# rotary_sewing.net
KiCad netlist of a schematic drawn in EAGLE
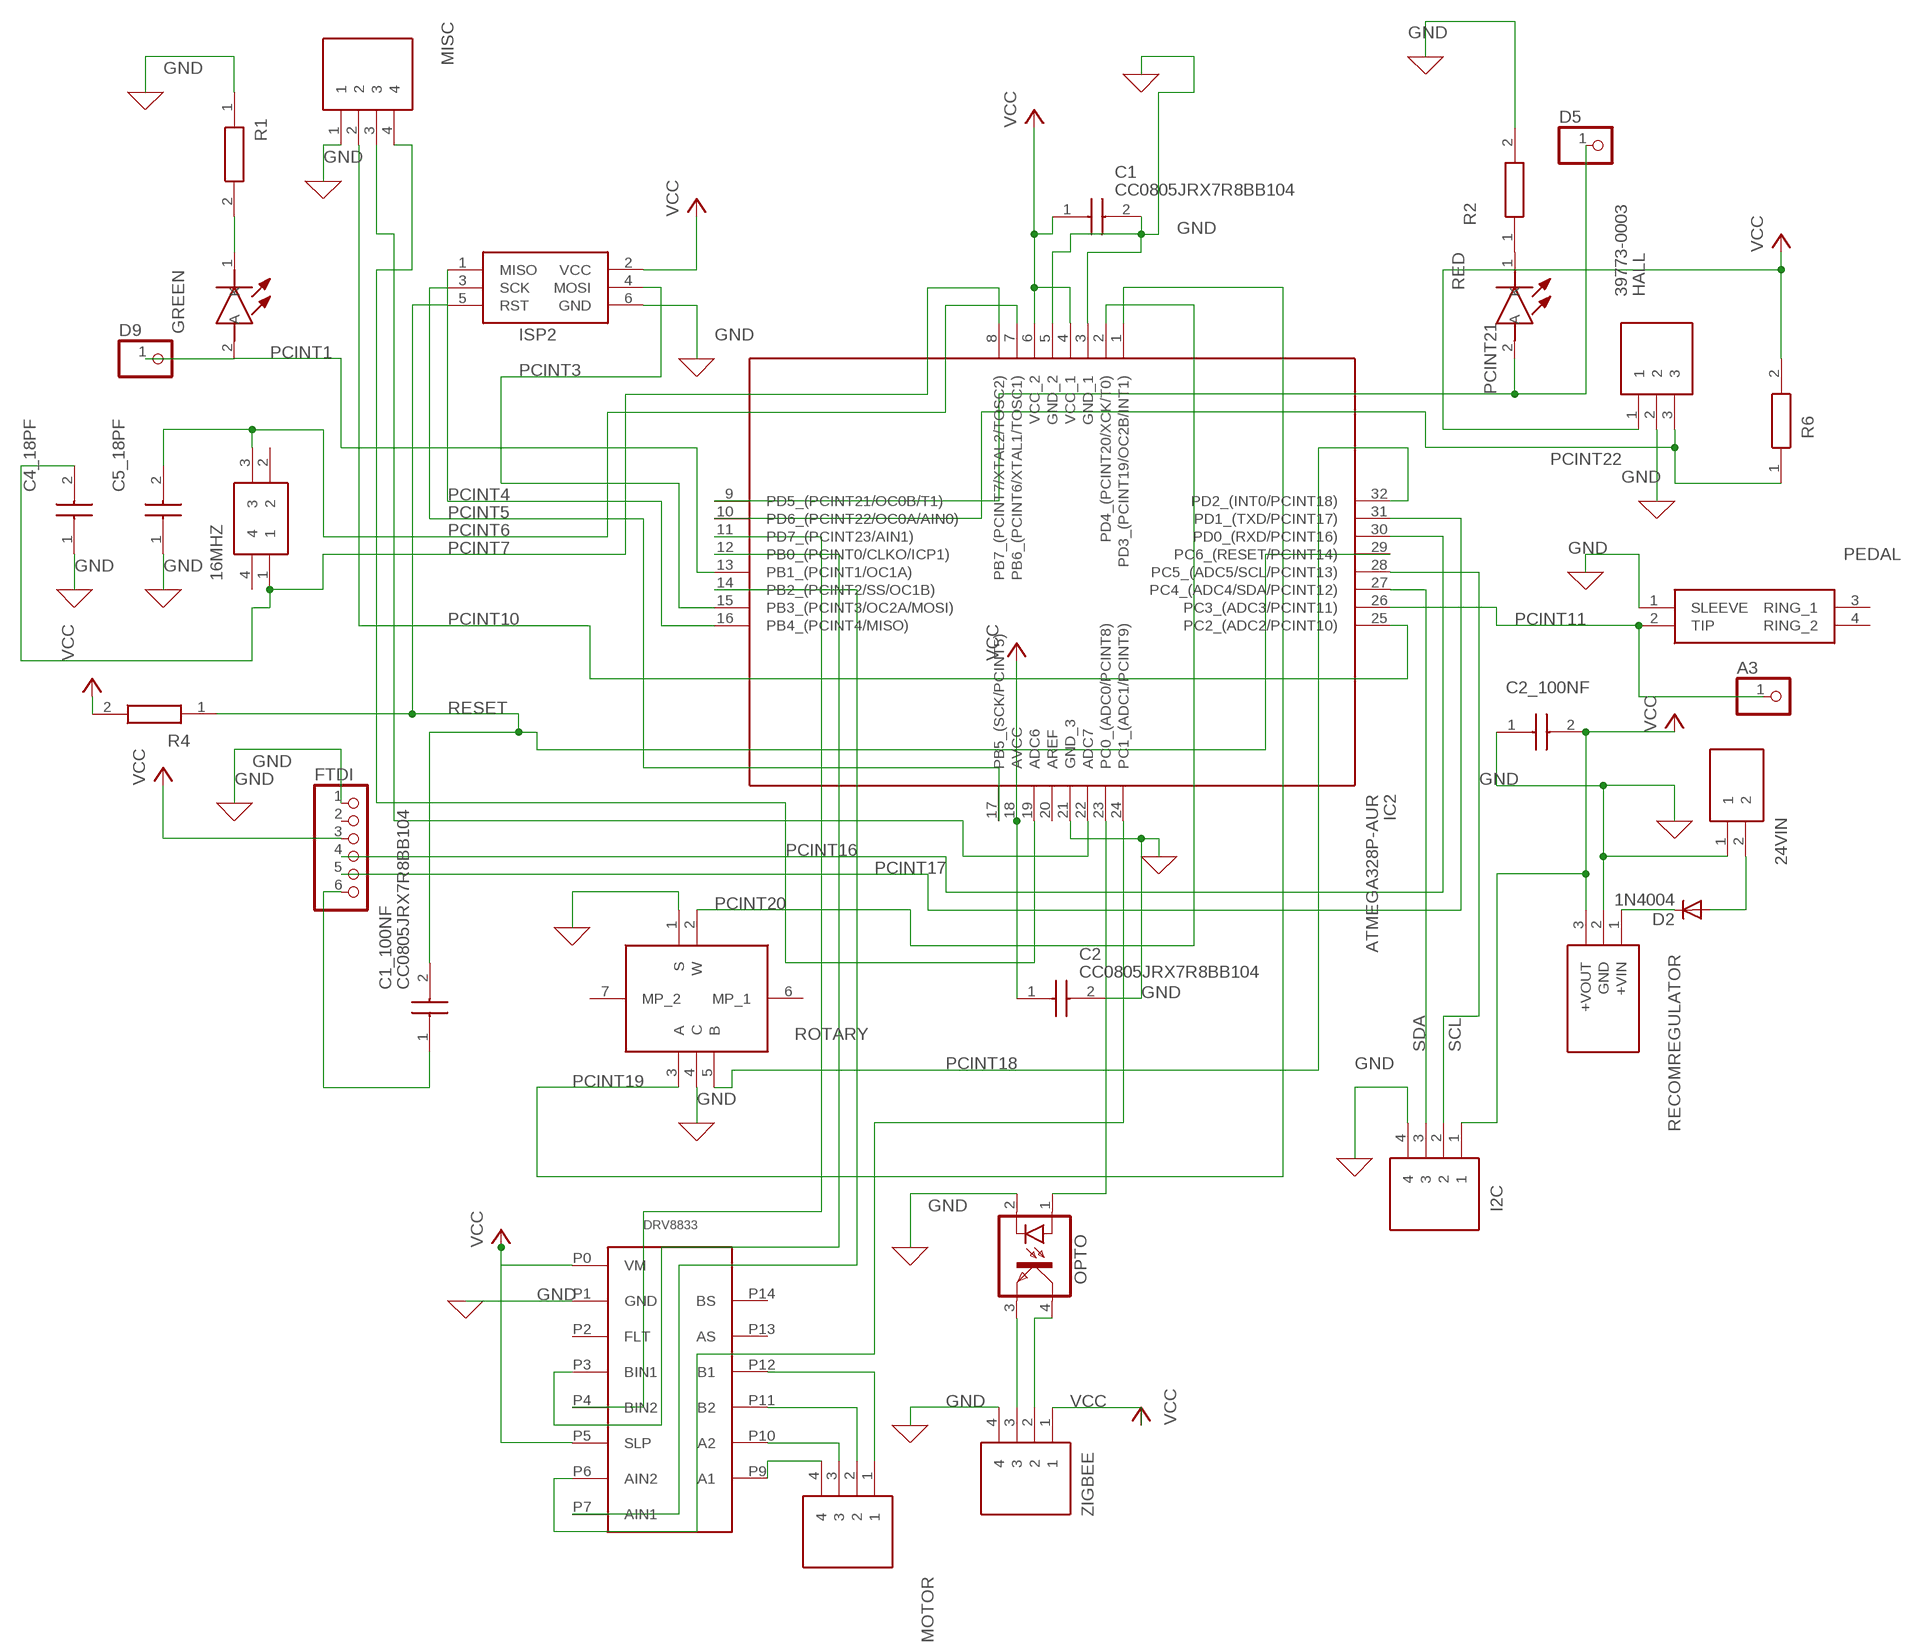
[diagram p0: schematic, sheet 1]

(export (version "E")
  (design (tool "Eeschema 10.0.6"))
  (components
    (comp (ref "16MHZ")
      (value "403C11E16M00000")
      (footprint "eagle-import:403C1XA32M00000")
      (fields (field (name "MOUSER_PART_NUMBER") "774-403C11E16M0"))
      (libsource (lib "eagle-import") (part "403C11E16M00000"))
    )
    (comp (ref "24VIN")
      (value "39773-0002")
      (footprint "eagle-import:SHDR2W110P0X254_1X2_554X650X10")
      (fields (field (name "MOUSER_PART_NUMBER") "538-39773-0002"))
      (libsource (lib "eagle-import") (part "39773-0002"))
    )
    (comp (ref "A3")
      (value "PINHD-1X1")
      (footprint "eagle-import:1X01")
      (libsource (lib "eagle-import") (part "PINHD-1X1"))
    )
    (comp (ref "C1")
      (value "CC0805JRX7R8BB104")
      (footprint "eagle-import:CAPC2012X135N")
      (fields (field (name "MOUSER_PART_NUMBER") "603-CC805JRX7R8BB104"))
      (libsource (lib "eagle-import") (part "CC0805JRX7R8BB104"))
    )
    (comp (ref "C1_100NF")
      (value "CC0805JRX7R8BB104")
      (footprint "eagle-import:CAPC2012X135N")
      (fields (field (name "MOUSER_PART_NUMBER") "603-CC805JRX7R8BB104"))
      (libsource (lib "eagle-import") (part "CC0805JRX7R8BB104"))
    )
    (comp (ref "C2")
      (value "CC0805JRX7R8BB104")
      (footprint "eagle-import:CAPC2012X135N")
      (fields (field (name "MOUSER_PART_NUMBER") "603-CC805JRX7R8BB104"))
      (libsource (lib "eagle-import") (part "CC0805JRX7R8BB104"))
    )
    (comp (ref "C2_100NF")
      (value "CC0805JRX7R8BB104")
      (footprint "eagle-import:CAPC2012X135N")
      (fields (field (name "MOUSER_PART_NUMBER") "603-CC805JRX7R8BB104"))
      (libsource (lib "eagle-import") (part "CC0805JRX7R8BB104"))
    )
    (comp (ref "C4_18PF")
      (value "C0805C180J5GACTU")
      (footprint "eagle-import:CAPC2012X88N")
      (fields (field (name "MOUSER_PART_NUMBER") "80-C0805C180J5G"))
      (libsource (lib "eagle-import") (part "C0805C180J5GACTU"))
    )
    (comp (ref "C5_18PF")
      (value "C0805C180J5GACTU")
      (footprint "eagle-import:CAPC2012X88N")
      (fields (field (name "MOUSER_PART_NUMBER") "80-C0805C180J5G"))
      (libsource (lib "eagle-import") (part "C0805C180J5GACTU"))
    )
    (comp (ref "D2")
      (value "1N4004")
      (footprint "eagle-import:DO41-10")
      (libsource (lib "eagle-import") (part "1N4004"))
    )
    (comp (ref "D5")
      (value "PINHD-1X1")
      (footprint "eagle-import:1X01")
      (libsource (lib "eagle-import") (part "PINHD-1X1"))
    )
    (comp (ref "D9")
      (value "PINHD-1X1")
      (footprint "eagle-import:1X01")
      (libsource (lib "eagle-import") (part "PINHD-1X1"))
    )
    (comp (ref "DRV8833")
      (value "DRV8833")
      (footprint "eagle-import:DRV8833")
      (libsource (lib "eagle-import") (part "DRV8833"))
    )
    (comp (ref "FTDI")
      (value "PINHD-1X6")
      (footprint "eagle-import:1X06")
      (libsource (lib "eagle-import") (part "PINHD-1X6"))
    )
    (comp (ref "GREEN")
      (value "LTST-C171GKT")
      (footprint "eagle-import:LEDC2012X90N")
      (fields (field (name "MOUSER_PART_NUMBER") "859-LTST-C171GKT"))
      (libsource (lib "eagle-import") (part "LTST-C171GKT"))
    )
    (comp (ref "HALL")
      (value "39773-0003")
      (footprint "eagle-import:SHDR3W80P0X254_1X3_808X650X101")
      (fields (field (name "MOUSER_PART_NUMBER") "538-39773-0003"))
      (libsource (lib "eagle-import") (part "39773-0003"))
    )
    (comp (ref "I2C")
      (value "39773-0004")
      (footprint "eagle-import:SHDR4W80P0X254_1X4_1062X650X10")
      (fields (field (name "MOUSER_PART_NUMBER") "538-39773-0004"))
      (libsource (lib "eagle-import") (part "39773-0004"))
    )
    (comp (ref "IC2")
      (value "ATMEGA328P-AUR")
      (footprint "eagle-import:QFP80P900X900X120-32N")
      (fields (field (name "MOUSER_PART_NUMBER") "556-ATMEGA328P-AUR"))
      (libsource (lib "eagle-import") (part "ATMEGA328P-AUR"))
    )
    (comp (ref "ISP2")
      (value "AVRISP-6")
      (footprint "eagle-import:AVRISP")
      (libsource (lib "eagle-import") (part "AVRISP-6"))
    )
    (comp (ref "MISC")
      (value "39773-0004")
      (footprint "eagle-import:SHDR4W80P0X254_1X4_1062X650X10")
      (fields (field (name "MOUSER_PART_NUMBER") "538-39773-0004"))
      (libsource (lib "eagle-import") (part "39773-0004"))
    )
    (comp (ref "MOTOR")
      (value "39773-0004")
      (footprint "eagle-import:SHDR4W80P0X254_1X4_1062X650X10")
      (fields (field (name "MOUSER_PART_NUMBER") "538-39773-0004"))
      (libsource (lib "eagle-import") (part "39773-0004"))
    )
    (comp (ref "OPTO")
      (value "PC817")
      (footprint "eagle-import:DIL04")
      (fields (field (name "MPN") "PC817X4J000F"))
      (libsource (lib "eagle-import") (part "PC817"))
    )
    (comp (ref "PEDAL")
      (value "SJ2-3574A-SMT-TR")
      (footprint "eagle-import:SJ23574ASMTTR")
      (fields (field (name "MOUSER_PART_NUMBER") "490-SJ2-3574A-SMT-TR"))
      (libsource (lib "eagle-import") (part "SJ2-3574A-SMT-TR"))
    )
    (comp (ref "R1")
      (value "RMC1_10K1001FTP")
      (footprint "eagle-import:RESC2012X65N")
      (fields
        (field (name "MANUFACTURER_PART_NUMBER") "RMC1/10K1001FTP")
        (field (name "MOUSER_PART_NUMBER") "791-RMC1/10K1001FTP")
      )
      (libsource (lib "eagle-import") (part "RMC1_10K1001FTP"))
    )
    (comp (ref "R2")
      (value "RMC1_10K1001FTP")
      (footprint "eagle-import:RESC2012X65N")
      (fields
        (field (name "MANUFACTURER_PART_NUMBER") "RMC1/10K1001FTP")
        (field (name "MOUSER_PART_NUMBER") "791-RMC1/10K1001FTP")
      )
      (libsource (lib "eagle-import") (part "RMC1_10K1001FTP"))
    )
    (comp (ref "R4")
      (value "ERA-6AED103V")
      (footprint "eagle-import:RESC2012X60N")
      (fields (field (name "MOUSER_PART_NUMBER") "667-ERA-6AED103V"))
      (libsource (lib "eagle-import") (part "ERA-6AED103V"))
    )
    (comp (ref "R6")
      (value "ERA-6AED103V")
      (footprint "eagle-import:RESC2012X60N")
      (fields (field (name "MOUSER_PART_NUMBER") "667-ERA-6AED103V"))
      (libsource (lib "eagle-import") (part "ERA-6AED103V"))
    )
    (comp (ref "RECOMREGULATOR")
      (value "R-78E3.3-1.0")
      (footprint "eagle-import:R-78E3.3-1.0")
      (fields (field (name "MOUSER_PART_NUMBER") "919-R-78E3.3-1.0"))
      (libsource (lib "eagle-import") (part "R-78E3.3-1.0"))
    )
    (comp (ref "RED")
      (value "LTST-C171KRKT")
      (footprint "eagle-import:LEDM2012X90N")
      (fields (field (name "MOUSER_PART_NUMBER") "859-LTST-C171KRKT"))
      (libsource (lib "eagle-import") (part "LTST-C171KRKT"))
    )
    (comp (ref "ROTARY")
      (value "PEC11L-4220F-S0015")
      (footprint "eagle-import:PEC11L4220FS0015")
      (fields (field (name "MOUSER_PART_NUMBER") "652-PEC11L4220FS0015"))
      (libsource (lib "eagle-import") (part "PEC11L-4220F-S0015"))
    )
    (comp (ref "ZIGBEE")
      (value "39773-0004")
      (footprint "eagle-import:SHDR4W80P0X254_1X4_1062X650X10")
      (fields (field (name "MOUSER_PART_NUMBER") "538-39773-0004"))
      (libsource (lib "eagle-import") (part "39773-0004"))
    )
  )
  (nets
    (net (code "1") (name "/PCINT1") (class "Default")
      (node (ref "D9") (pin "1") (pinfunction "1_1") (pintype "passive"))
      (node (ref "GREEN") (pin "2") (pinfunction "A_2") (pintype "bidirectional"))
      (node (ref "IC2") (pin "13") (pinfunction "PB1_(PCINT1/OC1A)_13") (pintype "input"))
    )
    (net (code "2") (name "/PCINT3") (class "Default")
      (node (ref "IC2") (pin "15") (pinfunction "PB3_(PCINT3/OC2A/MOSI)_15") (pintype "input"))
      (node (ref "ISP2") (pin "4") (pinfunction "MOSI_4") (pintype "output"))
    )
    (net (code "3") (name "/PCINT4") (class "Default")
      (node (ref "IC2") (pin "16") (pinfunction "PB4_(PCINT4/MISO)_16") (pintype "input"))
      (node (ref "ISP2") (pin "1") (pinfunction "MISO_1") (pintype "input"))
    )
    (net (code "4") (name "/PCINT5") (class "Default")
      (node (ref "IC2") (pin "17") (pinfunction "PB5_(SCK/PCINT5)_17") (pintype "input"))
      (node (ref "ISP2") (pin "3") (pinfunction "SCK_3") (pintype "output"))
    )
    (net (code "5") (name "/PCINT6") (class "Default")
      (node (ref "16MHZ") (pin "3") (pinfunction "3_3") (pintype "bidirectional"))
      (node (ref "C5_18PF") (pin "2") (pinfunction "2_2") (pintype "bidirectional"))
      (node (ref "IC2") (pin "7") (pinfunction "PB6_(PCINT6/XTAL1/TOSC1)_7") (pintype "input"))
    )
    (net (code "6") (name "/PCINT7") (class "Default")
      (node (ref "16MHZ") (pin "1") (pinfunction "1_1") (pintype "bidirectional"))
      (node (ref "C4_18PF") (pin "2") (pinfunction "2_2") (pintype "bidirectional"))
      (node (ref "IC2") (pin "8") (pinfunction "PB7_(PCINT7/XTAL2/TOSC2)_8") (pintype "input"))
    )
    (net (code "7") (name "/PCINT10") (class "Default")
      (node (ref "IC2") (pin "25") (pinfunction "PC2_(ADC2/PCINT10)_25") (pintype "input"))
      (node (ref "MISC") (pin "2") (pinfunction "2_2") (pintype "bidirectional"))
    )
    (net (code "8") (name "/PCINT11") (class "Default")
      (node (ref "A3") (pin "1") (pinfunction "1_1") (pintype "passive"))
      (node (ref "IC2") (pin "26") (pinfunction "PC3_(ADC3/PCINT11)_26") (pintype "input"))
      (node (ref "PEDAL") (pin "2") (pinfunction "TIP_2") (pintype "bidirectional"))
    )
    (net (code "9") (name "/PCINT16") (class "Default")
      (node (ref "FTDI") (pin "4") (pinfunction "4_4") (pintype "passive"))
      (node (ref "IC2") (pin "30") (pinfunction "PD0_(RXD/PCINT16)_30") (pintype "input"))
    )
    (net (code "10") (name "/PCINT17") (class "Default")
      (node (ref "FTDI") (pin "5") (pinfunction "5_5") (pintype "passive"))
      (node (ref "IC2") (pin "31") (pinfunction "PD1_(TXD/PCINT17)_31") (pintype "input"))
    )
    (net (code "11") (name "/PCINT18") (class "Default")
      (node (ref "IC2") (pin "32") (pinfunction "PD2_(INT0/PCINT18)_32") (pintype "input"))
      (node (ref "ROTARY") (pin "5") (pinfunction "B_5") (pintype "bidirectional"))
    )
    (net (code "12") (name "/PCINT19") (class "Default")
      (node (ref "IC2") (pin "1") (pinfunction "PD3_(PCINT19/OC2B/INT1)_1") (pintype "input"))
      (node (ref "ROTARY") (pin "3") (pinfunction "A_3") (pintype "bidirectional"))
    )
    (net (code "13") (name "/PCINT20") (class "Default")
      (node (ref "IC2") (pin "2") (pinfunction "PD4_(PCINT20/XCK/T0)_2") (pintype "input"))
      (node (ref "ROTARY") (pin "2") (pinfunction "W_2") (pintype "bidirectional"))
    )
    (net (code "14") (name "/PCINT21") (class "Default")
      (node (ref "D5") (pin "1") (pinfunction "1_1") (pintype "passive"))
      (node (ref "IC2") (pin "9") (pinfunction "PD5_(PCINT21/OC0B/T1)_9") (pintype "input"))
      (node (ref "RED") (pin "2") (pinfunction "A_2") (pintype "bidirectional"))
    )
    (net (code "15") (name "/PCINT22") (class "Default")
      (node (ref "HALL") (pin "3") (pinfunction "3_3") (pintype "bidirectional"))
      (node (ref "IC2") (pin "10") (pinfunction "PD6_(PCINT22/OC0A/AIN0)_10") (pintype "input"))
      (node (ref "R6") (pin "1") (pinfunction "1_1") (pintype "bidirectional"))
    )
    (net (code "16") (name "/RESET") (class "Default")
      (node (ref "C1_100NF") (pin "2") (pinfunction "2_2") (pintype "bidirectional"))
      (node (ref "IC2") (pin "29") (pinfunction "PC6_(RESET/PCINT14)_29") (pintype "input"))
      (node (ref "ISP2") (pin "5") (pinfunction "RST_5") (pintype "output"))
      (node (ref "R4") (pin "1") (pinfunction "1_1") (pintype "bidirectional"))
    )
    (net (code "17") (name "/SCL") (class "Default")
      (node (ref "I2C") (pin "2") (pinfunction "2_2") (pintype "bidirectional"))
      (node (ref "IC2") (pin "28") (pinfunction "PC5_(ADC5/SCL/PCINT13)_28") (pintype "input"))
    )
    (net (code "18") (name "/SDA") (class "Default")
      (node (ref "I2C") (pin "3") (pinfunction "3_3") (pintype "bidirectional"))
      (node (ref "IC2") (pin "27") (pinfunction "PC4_(ADC4/SDA/PCINT12)_27") (pintype "input"))
    )
    (net (code "19") (name "GND") (class "Default")
      (node (ref "24VIN") (pin "1") (pinfunction "1_1") (pintype "bidirectional"))
      (node (ref "C1") (pin "2") (pinfunction "2_2") (pintype "bidirectional"))
      (node (ref "C2") (pin "2") (pinfunction "2_2") (pintype "bidirectional"))
      (node (ref "C2_100NF") (pin "1") (pinfunction "1_1") (pintype "bidirectional"))
      (node (ref "C4_18PF") (pin "1") (pinfunction "1_1") (pintype "bidirectional"))
      (node (ref "C5_18PF") (pin "1") (pinfunction "1_1") (pintype "bidirectional"))
      (node (ref "DRV8833") (pin "P1") (pinfunction "GND_P1") (pintype "bidirectional"))
      (node (ref "FTDI") (pin "1") (pinfunction "1_1") (pintype "passive"))
      (node (ref "HALL") (pin "2") (pinfunction "2_2") (pintype "bidirectional"))
      (node (ref "I2C") (pin "4") (pinfunction "4_4") (pintype "bidirectional"))
      (node (ref "IC2") (pin "21") (pinfunction "GND_3_21") (pintype "power_in"))
      (node (ref "IC2") (pin "3") (pinfunction "GND_1_3") (pintype "power_in"))
      (node (ref "IC2") (pin "5") (pinfunction "GND_2_5") (pintype "power_in"))
      (node (ref "ISP2") (pin "6") (pinfunction "GND_6") (pintype "power_in"))
      (node (ref "MISC") (pin "1") (pinfunction "1_1") (pintype "bidirectional"))
      (node (ref "OPTO") (pin "2") (pinfunction "C_2") (pintype "passive"))
      (node (ref "PEDAL") (pin "1") (pinfunction "SLEEVE_1") (pintype "bidirectional"))
      (node (ref "R1") (pin "1") (pinfunction "1_1") (pintype "bidirectional"))
      (node (ref "R2") (pin "2") (pinfunction "2_2") (pintype "bidirectional"))
      (node (ref "RECOMREGULATOR") (pin "2") (pinfunction "GND_2") (pintype "bidirectional"))
      (node (ref "ROTARY") (pin "1") (pinfunction "S_1") (pintype "bidirectional"))
      (node (ref "ROTARY") (pin "4") (pinfunction "C_4") (pintype "bidirectional"))
      (node (ref "ZIGBEE") (pin "4") (pinfunction "4_4") (pintype "bidirectional"))
    )
    (net (code "20") (name "Net-(24VIN-Pad2)") (class "Default")
      (node (ref "24VIN") (pin "2") (pinfunction "2_2") (pintype "bidirectional"))
      (node (ref "D2") (pin "A") (pinfunction "A_A") (pintype "passive"))
    )
    (net (code "21") (name "Net-(C1_100NF-Pad1)") (class "Default")
      (node (ref "C1_100NF") (pin "1") (pinfunction "1_1") (pintype "bidirectional"))
      (node (ref "FTDI") (pin "6") (pinfunction "6_6") (pintype "passive"))
    )
    (net (code "22") (name "Net-(DRV8833-A1)") (class "Default")
      (node (ref "DRV8833") (pin "P9") (pinfunction "A1_P9") (pintype "bidirectional"))
      (node (ref "MOTOR") (pin "4") (pinfunction "4_4") (pintype "bidirectional"))
    )
    (net (code "23") (name "Net-(DRV8833-A2)") (class "Default")
      (node (ref "DRV8833") (pin "P10") (pinfunction "A2_P10") (pintype "bidirectional"))
      (node (ref "MOTOR") (pin "3") (pinfunction "3_3") (pintype "bidirectional"))
    )
    (net (code "24") (name "Net-(DRV8833-AIN1)") (class "Default")
      (node (ref "DRV8833") (pin "P7") (pinfunction "AIN1_P7") (pintype "bidirectional"))
      (node (ref "IC2") (pin "14") (pinfunction "PB2_(PCINT2/SS/OC1B)_14") (pintype "input"))
    )
    (net (code "25") (name "Net-(DRV8833-AIN2)") (class "Default")
      (node (ref "DRV8833") (pin "P6") (pinfunction "AIN2_P6") (pintype "bidirectional"))
      (node (ref "IC2") (pin "24") (pinfunction "PC1_(ADC1/PCINT9)_24") (pintype "input"))
    )
    (net (code "26") (name "Net-(DRV8833-B1)") (class "Default")
      (node (ref "DRV8833") (pin "P12") (pinfunction "B1_P12") (pintype "bidirectional"))
      (node (ref "MOTOR") (pin "1") (pinfunction "1_1") (pintype "bidirectional"))
    )
    (net (code "27") (name "Net-(DRV8833-B2)") (class "Default")
      (node (ref "DRV8833") (pin "P11") (pinfunction "B2_P11") (pintype "bidirectional"))
      (node (ref "MOTOR") (pin "2") (pinfunction "2_2") (pintype "bidirectional"))
    )
    (net (code "28") (name "Net-(DRV8833-BIN1)") (class "Default")
      (node (ref "DRV8833") (pin "P3") (pinfunction "BIN1_P3") (pintype "bidirectional"))
      (node (ref "IC2") (pin "12") (pinfunction "PB0_(PCINT0/CLKO/ICP1)_12") (pintype "output"))
    )
    (net (code "29") (name "Net-(DRV8833-BIN2)") (class "Default")
      (node (ref "DRV8833") (pin "P4") (pinfunction "BIN2_P4") (pintype "bidirectional"))
      (node (ref "IC2") (pin "11") (pinfunction "PD7_(PCINT23/AIN1)_11") (pintype "input"))
    )
    (net (code "30") (name "Net-(GREEN-K)") (class "Default")
      (node (ref "GREEN") (pin "1") (pinfunction "K_1") (pintype "bidirectional"))
      (node (ref "R1") (pin "2") (pinfunction "2_2") (pintype "bidirectional"))
    )
    (net (code "31") (name "Net-(IC2-ADC6)") (class "Default")
      (node (ref "IC2") (pin "19") (pinfunction "ADC6_19") (pintype "bidirectional"))
      (node (ref "MISC") (pin "4") (pinfunction "4_4") (pintype "bidirectional"))
    )
    (net (code "32") (name "Net-(IC2-ADC7)") (class "Default")
      (node (ref "IC2") (pin "22") (pinfunction "ADC7_22") (pintype "bidirectional"))
      (node (ref "MISC") (pin "3") (pinfunction "3_3") (pintype "bidirectional"))
    )
    (net (code "33") (name "Net-(IC2-PC0_(ADC0{slash}PCINT8))") (class "Default")
      (node (ref "IC2") (pin "23") (pinfunction "PC0_(ADC0/PCINT8)_23") (pintype "input"))
      (node (ref "OPTO") (pin "1") (pinfunction "A_1") (pintype "passive"))
    )
    (net (code "34") (name "Net-(OPTO-COL)") (class "Default")
      (node (ref "OPTO") (pin "4") (pinfunction "COL_4") (pintype "passive"))
      (node (ref "ZIGBEE") (pin "2") (pinfunction "2_2") (pintype "bidirectional"))
    )
    (net (code "35") (name "Net-(OPTO-EMIT)") (class "Default")
      (node (ref "OPTO") (pin "3") (pinfunction "EMIT_3") (pintype "passive"))
      (node (ref "ZIGBEE") (pin "3") (pinfunction "3_3") (pintype "bidirectional"))
    )
    (net (code "36") (name "Net-(RECOMREGULATOR-+VIN)") (class "Default")
      (node (ref "D2") (pin "C") (pinfunction "C_C") (pintype "passive"))
      (node (ref "RECOMREGULATOR") (pin "1") (pinfunction "+VIN_1") (pintype "bidirectional"))
    )
    (net (code "37") (name "Net-(RED-K)") (class "Default")
      (node (ref "R2") (pin "1") (pinfunction "1_1") (pintype "bidirectional"))
      (node (ref "RED") (pin "1") (pinfunction "K_1") (pintype "bidirectional"))
    )
    (net (code "38") (name "VCC") (class "Default")
      (node (ref "C1") (pin "1") (pinfunction "1_1") (pintype "bidirectional"))
      (node (ref "C2") (pin "1") (pinfunction "1_1") (pintype "bidirectional"))
      (node (ref "C2_100NF") (pin "2") (pinfunction "2_2") (pintype "bidirectional"))
      (node (ref "DRV8833") (pin "P0") (pinfunction "VM_P0") (pintype "bidirectional"))
      (node (ref "DRV8833") (pin "P5") (pinfunction "SLP_P5") (pintype "bidirectional"))
      (node (ref "FTDI") (pin "3") (pinfunction "3_3") (pintype "passive"))
      (node (ref "HALL") (pin "1") (pinfunction "1_1") (pintype "bidirectional"))
      (node (ref "I2C") (pin "1") (pinfunction "1_1") (pintype "bidirectional"))
      (node (ref "IC2") (pin "18") (pinfunction "AVCC_18") (pintype "power_in"))
      (node (ref "IC2") (pin "4") (pinfunction "VCC_1_4") (pintype "power_in"))
      (node (ref "IC2") (pin "6") (pinfunction "VCC_2_6") (pintype "power_in"))
      (node (ref "ISP2") (pin "2") (pinfunction "VCC_2") (pintype "power_in"))
      (node (ref "R4") (pin "2") (pinfunction "2_2") (pintype "bidirectional"))
      (node (ref "R6") (pin "2") (pinfunction "2_2") (pintype "bidirectional"))
      (node (ref "RECOMREGULATOR") (pin "3") (pinfunction "+VOUT_3") (pintype "bidirectional"))
      (node (ref "ZIGBEE") (pin "1") (pinfunction "1_1") (pintype "bidirectional"))
    )
    (net (code "39") (name "unconnected-(16MHZ-Pad2)") (class "Default")
      (node (ref "16MHZ") (pin "2") (pinfunction "2_2") (pintype "bidirectional"))
    )
    (net (code "40") (name "unconnected-(16MHZ-Pad4)") (class "Default")
      (node (ref "16MHZ") (pin "4") (pinfunction "4_4") (pintype "bidirectional"))
    )
    (net (code "41") (name "unconnected-(DRV8833-AS-PadP13)") (class "Default")
      (node (ref "DRV8833") (pin "P13") (pinfunction "AS_P13") (pintype "bidirectional"))
    )
    (net (code "42") (name "unconnected-(DRV8833-BS-PadP14)") (class "Default")
      (node (ref "DRV8833") (pin "P14") (pinfunction "BS_P14") (pintype "bidirectional"))
    )
    (net (code "43") (name "unconnected-(DRV8833-FLT-PadP2)") (class "Default")
      (node (ref "DRV8833") (pin "P2") (pinfunction "FLT_P2") (pintype "bidirectional"))
    )
    (net (code "44") (name "unconnected-(FTDI-Pad2)") (class "Default")
      (node (ref "FTDI") (pin "2") (pinfunction "2_2") (pintype "passive"))
    )
    (net (code "45") (name "unconnected-(IC2-AREF-Pad20)") (class "Default")
      (node (ref "IC2") (pin "20") (pinfunction "AREF_20") (pintype "input"))
    )
    (net (code "46") (name "unconnected-(PEDAL-RING_1-Pad3)") (class "Default")
      (node (ref "PEDAL") (pin "3") (pinfunction "RING_1_3") (pintype "bidirectional"))
    )
    (net (code "47") (name "unconnected-(PEDAL-RING_2-Pad4)") (class "Default")
      (node (ref "PEDAL") (pin "4") (pinfunction "RING_2_4") (pintype "bidirectional"))
    )
    (net (code "48") (name "unconnected-(ROTARY-MP_1-Pad6)") (class "Default")
      (node (ref "ROTARY") (pin "6") (pinfunction "MP_1_6") (pintype "bidirectional"))
    )
    (net (code "49") (name "unconnected-(ROTARY-MP_2-Pad7)") (class "Default")
      (node (ref "ROTARY") (pin "7") (pinfunction "MP_2_7") (pintype "bidirectional"))
    )
  )
)
